# linistepper_with_aligned_transistors_my_.net
KiCad netlist of a schematic drawn in EAGLE
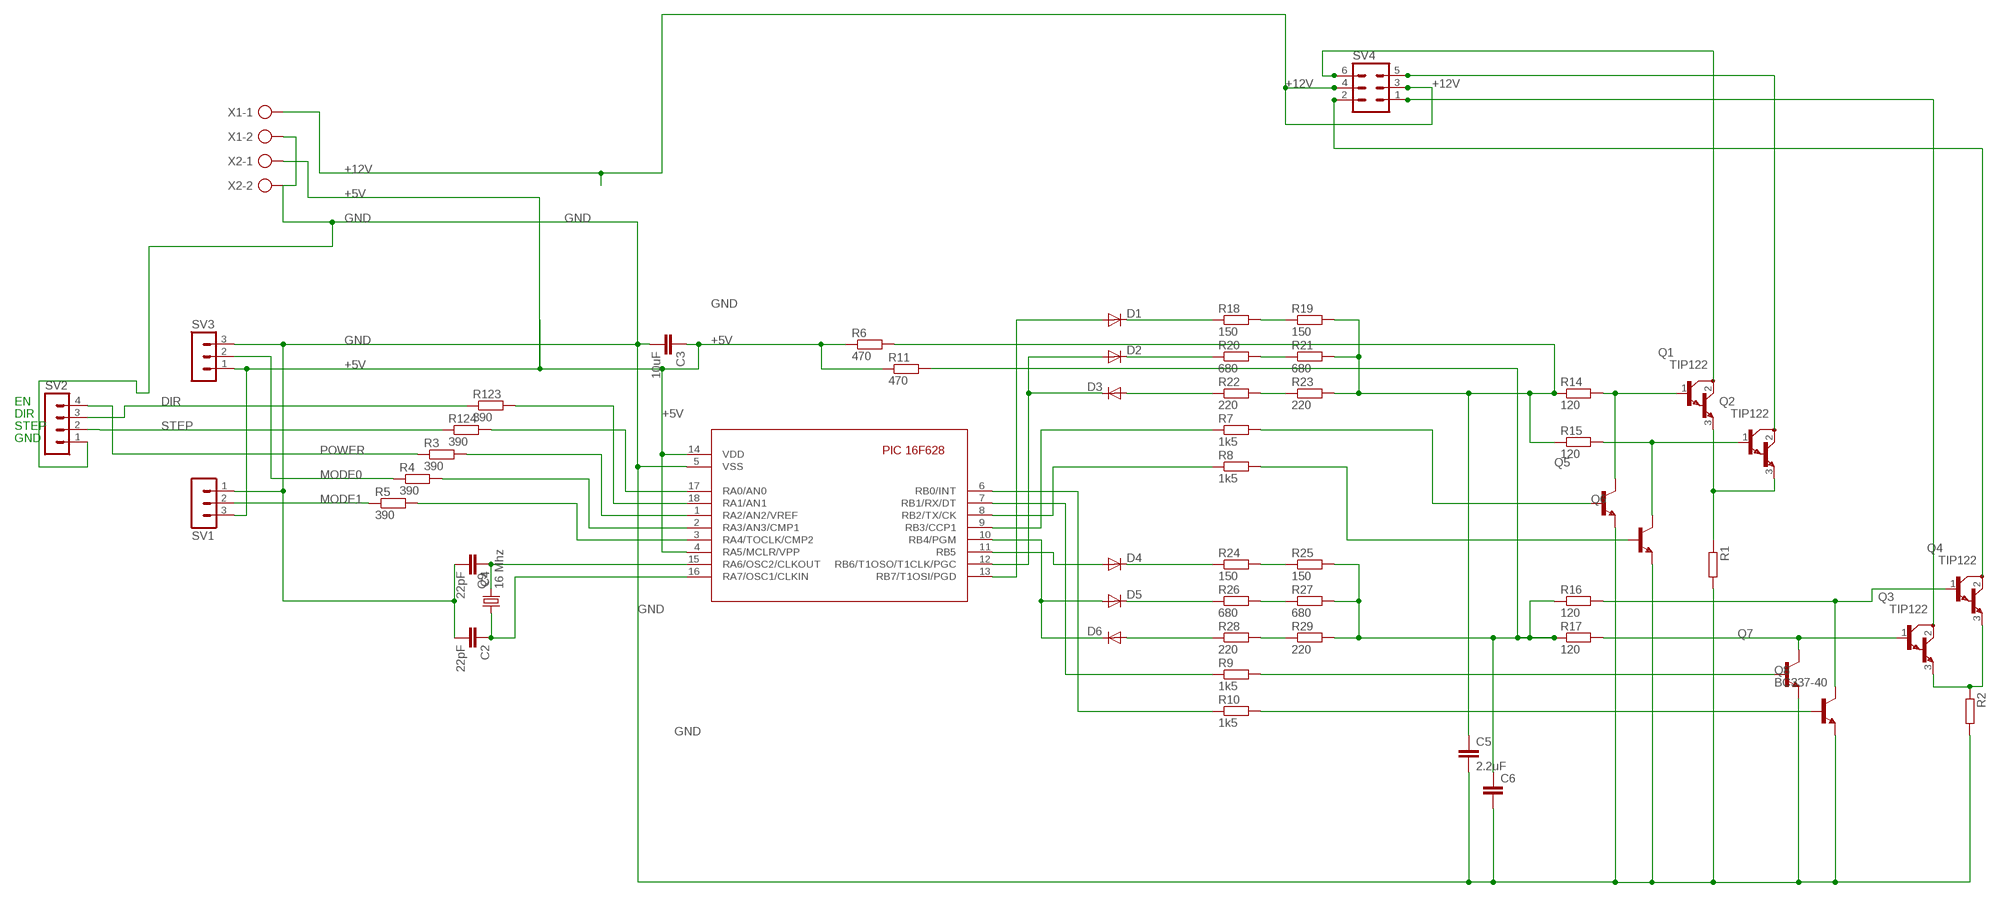
[diagram p0: schematic, sheet 1]

(export (version "E")
  (design (tool "Eeschema 10.0.6"))
  (components
    (comp (ref "C2")
      (value "22pF")
      (footprint "eagle-import:C025-024X044")
      (libsource (lib "eagle-import") (part "C-EU025-024X044"))
    )
    (comp (ref "C3")
      (value "10uF")
      (footprint "eagle-import:C025-040X050")
      (libsource (lib "eagle-import") (part "C-EU025-040X050"))
    )
    (comp (ref "C4")
      (value "22pF")
      (footprint "eagle-import:C025-024X044")
      (libsource (lib "eagle-import") (part "C-EU025-024X044"))
    )
    (comp (ref "C5")
      (value "2.2uF")
      (footprint "eagle-import:C050-024X044")
      (libsource (lib "eagle-import") (part "C-EU050-024X044"))
    )
    (comp (ref "C6")
      (value "C-EU050-024X044")
      (footprint "eagle-import:C050-024X044")
      (libsource (lib "eagle-import") (part "C-EU050-024X044"))
    )
    (comp (ref "D1")
      (value "1N4148")
      (footprint "eagle-import:DO35-10")
      (libsource (lib "eagle-import") (part "1N4148"))
    )
    (comp (ref "D2")
      (value "1N4148")
      (footprint "eagle-import:DO35-10")
      (libsource (lib "eagle-import") (part "1N4148"))
    )
    (comp (ref "D3")
      (value "1N4148")
      (footprint "eagle-import:DO35-10")
      (libsource (lib "eagle-import") (part "1N4148"))
    )
    (comp (ref "D4")
      (value "1N4148")
      (footprint "eagle-import:DO35-10")
      (libsource (lib "eagle-import") (part "1N4148"))
    )
    (comp (ref "D5")
      (value "1N4148")
      (footprint "eagle-import:DO35-10")
      (libsource (lib "eagle-import") (part "1N4148"))
    )
    (comp (ref "D6")
      (value "1N4148")
      (footprint "eagle-import:DO35-10")
      (libsource (lib "eagle-import") (part "1N4148"))
    )
    (comp (ref "Q1")
      (value "TIP122")
      (footprint "eagle-import:TO220")
      (libsource (lib "eagle-import") (part "TIP122"))
    )
    (comp (ref "Q2")
      (value "TIP122")
      (footprint "eagle-import:TO220")
      (libsource (lib "eagle-import") (part "TIP122"))
    )
    (comp (ref "Q3")
      (value "TIP122")
      (footprint "eagle-import:TO220")
      (libsource (lib "eagle-import") (part "TIP122"))
    )
    (comp (ref "Q4")
      (value "TIP122")
      (footprint "eagle-import:TO220")
      (libsource (lib "eagle-import") (part "TIP122"))
    )
    (comp (ref "Q5")
      (value "BC337-40")
      (footprint "eagle-import:TO92")
      (libsource (lib "eagle-import") (part "BC337-40"))
    )
    (comp (ref "Q6")
      (value "BC337-40")
      (footprint "eagle-import:TO92")
      (libsource (lib "eagle-import") (part "BC337-40"))
    )
    (comp (ref "Q7")
      (value "BC337-40")
      (footprint "eagle-import:TO92")
      (libsource (lib "eagle-import") (part "BC337-40"))
    )
    (comp (ref "Q8")
      (value "BC337-40")
      (footprint "eagle-import:TO92")
      (libsource (lib "eagle-import") (part "BC337-40"))
    )
    (comp (ref "Q9")
      (value "16 Mhz")
      (footprint "eagle-import:HC49_S")
      (libsource (lib "eagle-import") (part "CRYTALHC49S"))
    )
    (comp (ref "R1")
      (value "R-EU_0922/22")
      (footprint "eagle-import:0922_22")
      (libsource (lib "eagle-import") (part "R-EU_0922/22"))
    )
    (comp (ref "R2")
      (value "R-EU_0922/22")
      (footprint "eagle-import:0922_22")
      (libsource (lib "eagle-import") (part "R-EU_0922/22"))
    )
    (comp (ref "R3")
      (value "390")
      (footprint "eagle-import:0207_2V")
      (libsource (lib "eagle-import") (part "resistor_R-EU_0207/2V"))
    )
    (comp (ref "R4")
      (value "390")
      (footprint "eagle-import:0411V")
      (libsource (lib "eagle-import") (part "resistor_R-EU_0411/3V"))
    )
    (comp (ref "R5")
      (value "390")
      (footprint "eagle-import:0207_5V")
      (libsource (lib "eagle-import") (part "R-EU_0207/5V"))
    )
    (comp (ref "R6")
      (value "470")
      (footprint "eagle-import:0207_10")
      (libsource (lib "eagle-import") (part "R-EU_0207/10"))
    )
    (comp (ref "R7")
      (value "1k5")
      (footprint "eagle-import:0207_10")
      (libsource (lib "eagle-import") (part "R-EU_0207/10"))
    )
    (comp (ref "R8")
      (value "1k5")
      (footprint "eagle-import:0207_7")
      (libsource (lib "eagle-import") (part "resistor_R-EU_0207/7"))
    )
    (comp (ref "R9")
      (value "1k5")
      (footprint "eagle-import:0207_5V")
      (libsource (lib "eagle-import") (part "resistor_R-EU_0207/5V"))
    )
    (comp (ref "R10")
      (value "1k5")
      (footprint "eagle-import:0207_5V")
      (libsource (lib "eagle-import") (part "resistor_R-EU_0207/5V"))
    )
    (comp (ref "R11")
      (value "470")
      (footprint "eagle-import:0207_7")
      (libsource (lib "eagle-import") (part "resistor_R-EU_0207/7"))
    )
    (comp (ref "R14")
      (value "120")
      (footprint "eagle-import:0207_10")
      (libsource (lib "eagle-import") (part "R-EU_0207/10"))
    )
    (comp (ref "R15")
      (value "120")
      (footprint "eagle-import:0207_7")
      (libsource (lib "eagle-import") (part "resistor_R-EU_0207/7"))
    )
    (comp (ref "R16")
      (value "120")
      (footprint "eagle-import:0207_5V")
      (libsource (lib "eagle-import") (part "resistor_R-EU_0207/5V"))
    )
    (comp (ref "R17")
      (value "120")
      (footprint "eagle-import:0207_5V")
      (libsource (lib "eagle-import") (part "resistor_R-EU_0207/5V"))
    )
    (comp (ref "R18")
      (value "150")
      (footprint "eagle-import:0207_2V")
      (libsource (lib "eagle-import") (part "R-EU_0207/2V"))
    )
    (comp (ref "R19")
      (value "150")
      (footprint "eagle-import:0207_2V")
      (libsource (lib "eagle-import") (part "R-EU_0207/2V"))
    )
    (comp (ref "R20")
      (value "680")
      (footprint "eagle-import:0207_2V")
      (libsource (lib "eagle-import") (part "R-EU_0207/2V"))
    )
    (comp (ref "R21")
      (value "680")
      (footprint "eagle-import:0207_2V")
      (libsource (lib "eagle-import") (part "R-EU_0207/2V"))
    )
    (comp (ref "R22")
      (value "220")
      (footprint "eagle-import:0207_2V")
      (libsource (lib "eagle-import") (part "R-EU_0207/2V"))
    )
    (comp (ref "R23")
      (value "220")
      (footprint "eagle-import:0207_2V")
      (libsource (lib "eagle-import") (part "R-EU_0207/2V"))
    )
    (comp (ref "R24")
      (value "150")
      (footprint "eagle-import:0207_2V")
      (libsource (lib "eagle-import") (part "R-EU_0207/2V"))
    )
    (comp (ref "R25")
      (value "150")
      (footprint "eagle-import:0207_2V")
      (libsource (lib "eagle-import") (part "R-EU_0207/2V"))
    )
    (comp (ref "R26")
      (value "680")
      (footprint "eagle-import:0207_2V")
      (libsource (lib "eagle-import") (part "R-EU_0207/2V"))
    )
    (comp (ref "R27")
      (value "680")
      (footprint "eagle-import:0207_2V")
      (libsource (lib "eagle-import") (part "R-EU_0207/2V"))
    )
    (comp (ref "R28")
      (value "220")
      (footprint "eagle-import:0207_2V")
      (libsource (lib "eagle-import") (part "R-EU_0207/2V"))
    )
    (comp (ref "R29")
      (value "220")
      (footprint "eagle-import:0207_2V")
      (libsource (lib "eagle-import") (part "R-EU_0207/2V"))
    )
    (comp (ref "R123")
      (value "390")
      (footprint "eagle-import:0207_2V")
      (libsource (lib "eagle-import") (part "R-EU_0207/2V"))
    )
    (comp (ref "R124")
      (value "390")
      (footprint "eagle-import:0207_2V")
      (libsource (lib "eagle-import") (part "R-EU_0207/2V"))
    )
    (comp (ref "SV1")
      (value "MA03-1")
      (footprint "eagle-import:MA03-1")
      (libsource (lib "eagle-import") (part "MA03-1"))
    )
    (comp (ref "SV2")
      (value "MA04-1")
      (footprint "eagle-import:MA04-1")
      (libsource (lib "eagle-import") (part "MA04-1"))
    )
    (comp (ref "SV3")
      (value "MA03-1")
      (footprint "eagle-import:MA03-1")
      (libsource (lib "eagle-import") (part "MA03-1"))
    )
    (comp (ref "SV4")
      (value "MA03-2")
      (footprint "eagle-import:MA03-2")
      (libsource (lib "eagle-import") (part "MA03-2"))
    )
    (comp (ref "U$1")
      (value "16F628")
      (footprint "eagle-import:PIC16F628-18-LEAD-PDIP")
      (libsource (lib "eagle-import") (part "16F628"))
    )
    (comp (ref "X1")
      (value "AK300/2")
      (footprint "eagle-import:AK300_2")
      (libsource (lib "eagle-import") (part "AK300/2"))
    )
    (comp (ref "X2")
      (value "AK300/2")
      (footprint "eagle-import:AK300_2")
      (libsource (lib "eagle-import") (part "AK300/2"))
    )
  )
  (nets
    (net (code "1") (name "/+5V") (class "Default")
      (node (ref "C3") (pin "1") (pinfunction "1_1") (pintype "passive"))
      (node (ref "R11") (pin "1") (pinfunction "1_1") (pintype "passive"))
      (node (ref "R6") (pin "1") (pinfunction "1_1") (pintype "passive"))
      (node (ref "SV1") (pin "3") (pinfunction "3_3") (pintype "passive"))
      (node (ref "SV3") (pin "1") (pinfunction "1_1") (pintype "passive"))
      (node (ref "U$1") (pin "14") (pinfunction "VDD_14") (pintype "input"))
      (node (ref "U$1") (pin "4") (pinfunction "RA5/MCLR/VPP_4") (pintype "bidirectional"))
      (node (ref "X2") (pin "1") (pinfunction "KL_1") (pintype "passive"))
    )
    (net (code "2") (name "/+12V") (class "Default")
      (node (ref "SV4") (pin "3") (pinfunction "3_3") (pintype "passive"))
      (node (ref "SV4") (pin "4") (pinfunction "4_4") (pintype "passive"))
      (node (ref "X1") (pin "1") (pinfunction "KL_1") (pintype "passive"))
    )
    (net (code "3") (name "/DIR") (class "Default")
      (node (ref "R123") (pin "1") (pinfunction "1_1") (pintype "passive"))
      (node (ref "SV2") (pin "3") (pinfunction "3_3") (pintype "passive"))
    )
    (net (code "4") (name "/GND") (class "Default")
      (node (ref "C2") (pin "2") (pinfunction "2_2") (pintype "passive"))
      (node (ref "C3") (pin "2") (pinfunction "2_2") (pintype "passive"))
      (node (ref "C4") (pin "2") (pinfunction "2_2") (pintype "passive"))
      (node (ref "C5") (pin "2") (pinfunction "2_2") (pintype "passive"))
      (node (ref "C6") (pin "2") (pinfunction "2_2") (pintype "passive"))
      (node (ref "Q5") (pin "1") (pinfunction "E_1") (pintype "passive"))
      (node (ref "Q6") (pin "1") (pinfunction "E_1") (pintype "passive"))
      (node (ref "Q7") (pin "1") (pinfunction "E_1") (pintype "passive"))
      (node (ref "Q8") (pin "1") (pinfunction "E_1") (pintype "passive"))
      (node (ref "R1") (pin "2") (pinfunction "2_2") (pintype "passive"))
      (node (ref "R2") (pin "2") (pinfunction "2_2") (pintype "passive"))
      (node (ref "SV1") (pin "1") (pinfunction "1_1") (pintype "passive"))
      (node (ref "SV2") (pin "1") (pinfunction "1_1") (pintype "passive"))
      (node (ref "SV3") (pin "3") (pinfunction "3_3") (pintype "passive"))
      (node (ref "U$1") (pin "5") (pinfunction "VSS_5") (pintype "input"))
      (node (ref "X1") (pin "2") (pinfunction "KL_2") (pintype "passive"))
      (node (ref "X2") (pin "2") (pinfunction "KL_2") (pintype "passive"))
    )
    (net (code "5") (name "/MODE0") (class "Default")
      (node (ref "R4") (pin "1") (pinfunction "1_1") (pintype "passive"))
      (node (ref "SV3") (pin "2") (pinfunction "2_2") (pintype "passive"))
    )
    (net (code "6") (name "/MODE1") (class "Default")
      (node (ref "R5") (pin "1") (pinfunction "1_1") (pintype "passive"))
      (node (ref "SV1") (pin "2") (pinfunction "2_2") (pintype "passive"))
    )
    (net (code "7") (name "/POWER") (class "Default")
      (node (ref "R3") (pin "1") (pinfunction "1_1") (pintype "passive"))
      (node (ref "SV2") (pin "4") (pinfunction "4_4") (pintype "passive"))
    )
    (net (code "8") (name "/STEP") (class "Default")
      (node (ref "R124") (pin "1") (pinfunction "1_1") (pintype "passive"))
      (node (ref "SV2") (pin "2") (pinfunction "2_2") (pintype "passive"))
    )
    (net (code "9") (name "Net-(C5-Pad1)") (class "Default")
      (node (ref "C5") (pin "1") (pinfunction "1_1") (pintype "passive"))
      (node (ref "R14") (pin "1") (pinfunction "1_1") (pintype "passive"))
      (node (ref "R15") (pin "1") (pinfunction "1_1") (pintype "passive"))
      (node (ref "R19") (pin "2") (pinfunction "2_2") (pintype "passive"))
      (node (ref "R21") (pin "2") (pinfunction "2_2") (pintype "passive"))
      (node (ref "R23") (pin "2") (pinfunction "2_2") (pintype "passive"))
      (node (ref "R6") (pin "2") (pinfunction "2_2") (pintype "passive"))
    )
    (net (code "10") (name "Net-(C6-Pad1)") (class "Default")
      (node (ref "C6") (pin "1") (pinfunction "1_1") (pintype "passive"))
      (node (ref "R11") (pin "2") (pinfunction "2_2") (pintype "passive"))
      (node (ref "R16") (pin "1") (pinfunction "1_1") (pintype "passive"))
      (node (ref "R17") (pin "1") (pinfunction "1_1") (pintype "passive"))
      (node (ref "R25") (pin "2") (pinfunction "2_2") (pintype "passive"))
      (node (ref "R27") (pin "2") (pinfunction "2_2") (pintype "passive"))
      (node (ref "R29") (pin "2") (pinfunction "2_2") (pintype "passive"))
    )
    (net (code "11") (name "Net-(D1-PadC)") (class "Default")
      (node (ref "D1") (pin "C") (pinfunction "C_C") (pintype "passive"))
      (node (ref "R18") (pin "1") (pinfunction "1_1") (pintype "passive"))
    )
    (net (code "12") (name "Net-(D2-PadC)") (class "Default")
      (node (ref "D2") (pin "C") (pinfunction "C_C") (pintype "passive"))
      (node (ref "R20") (pin "1") (pinfunction "1_1") (pintype "passive"))
    )
    (net (code "13") (name "Net-(D3-PadA)") (class "Default")
      (node (ref "D3") (pin "A") (pinfunction "A_A") (pintype "passive"))
      (node (ref "R22") (pin "1") (pinfunction "1_1") (pintype "passive"))
    )
    (net (code "14") (name "Net-(D4-PadC)") (class "Default")
      (node (ref "D4") (pin "C") (pinfunction "C_C") (pintype "passive"))
      (node (ref "R24") (pin "1") (pinfunction "1_1") (pintype "passive"))
    )
    (net (code "15") (name "Net-(D5-PadC)") (class "Default")
      (node (ref "D5") (pin "C") (pinfunction "C_C") (pintype "passive"))
      (node (ref "R26") (pin "1") (pinfunction "1_1") (pintype "passive"))
    )
    (net (code "16") (name "Net-(D6-PadA)") (class "Default")
      (node (ref "D6") (pin "A") (pinfunction "A_A") (pintype "passive"))
      (node (ref "R28") (pin "1") (pinfunction "1_1") (pintype "passive"))
    )
    (net (code "17") (name "Net-(Q1-B)") (class "Default")
      (node (ref "Q1") (pin "1") (pinfunction "B_1") (pintype "passive"))
      (node (ref "Q5") (pin "3") (pinfunction "C_3") (pintype "passive"))
      (node (ref "R14") (pin "2") (pinfunction "2_2") (pintype "passive"))
    )
    (net (code "18") (name "Net-(Q1-C)") (class "Default")
      (node (ref "Q1") (pin "2") (pinfunction "C_2") (pintype "passive"))
      (node (ref "SV4") (pin "6") (pinfunction "6_6") (pintype "passive"))
    )
    (net (code "19") (name "Net-(Q1-E)") (class "Default")
      (node (ref "Q1") (pin "3") (pinfunction "E_3") (pintype "passive"))
      (node (ref "Q2") (pin "3") (pinfunction "E_3") (pintype "passive"))
      (node (ref "R1") (pin "1") (pinfunction "1_1") (pintype "passive"))
    )
    (net (code "20") (name "Net-(Q2-B)") (class "Default")
      (node (ref "Q2") (pin "1") (pinfunction "B_1") (pintype "passive"))
      (node (ref "Q6") (pin "3") (pinfunction "C_3") (pintype "passive"))
      (node (ref "R15") (pin "2") (pinfunction "2_2") (pintype "passive"))
    )
    (net (code "21") (name "Net-(Q2-C)") (class "Default")
      (node (ref "Q2") (pin "2") (pinfunction "C_2") (pintype "passive"))
      (node (ref "SV4") (pin "5") (pinfunction "5_5") (pintype "passive"))
    )
    (net (code "22") (name "Net-(Q3-B)") (class "Default")
      (node (ref "Q3") (pin "1") (pinfunction "B_1") (pintype "passive"))
      (node (ref "Q7") (pin "3") (pinfunction "C_3") (pintype "passive"))
      (node (ref "R17") (pin "2") (pinfunction "2_2") (pintype "passive"))
    )
    (net (code "23") (name "Net-(Q3-C)") (class "Default")
      (node (ref "Q3") (pin "2") (pinfunction "C_2") (pintype "passive"))
      (node (ref "SV4") (pin "1") (pinfunction "1_1") (pintype "passive"))
    )
    (net (code "24") (name "Net-(Q3-E)") (class "Default")
      (node (ref "Q3") (pin "3") (pinfunction "E_3") (pintype "passive"))
      (node (ref "Q4") (pin "3") (pinfunction "E_3") (pintype "passive"))
      (node (ref "R2") (pin "1") (pinfunction "1_1") (pintype "passive"))
    )
    (net (code "25") (name "Net-(Q4-B)") (class "Default")
      (node (ref "Q4") (pin "1") (pinfunction "B_1") (pintype "passive"))
      (node (ref "Q8") (pin "3") (pinfunction "C_3") (pintype "passive"))
      (node (ref "R16") (pin "2") (pinfunction "2_2") (pintype "passive"))
    )
    (net (code "26") (name "Net-(Q4-C)") (class "Default")
      (node (ref "Q4") (pin "2") (pinfunction "C_2") (pintype "passive"))
      (node (ref "SV4") (pin "2") (pinfunction "2_2") (pintype "passive"))
    )
    (net (code "27") (name "Net-(Q5-B)") (class "Default")
      (node (ref "Q5") (pin "2") (pinfunction "B_2") (pintype "passive"))
      (node (ref "R7") (pin "2") (pinfunction "2_2") (pintype "passive"))
    )
    (net (code "28") (name "Net-(Q6-B)") (class "Default")
      (node (ref "Q6") (pin "2") (pinfunction "B_2") (pintype "passive"))
      (node (ref "R8") (pin "2") (pinfunction "2_2") (pintype "passive"))
    )
    (net (code "29") (name "Net-(Q7-B)") (class "Default")
      (node (ref "Q7") (pin "2") (pinfunction "B_2") (pintype "passive"))
      (node (ref "R9") (pin "2") (pinfunction "2_2") (pintype "passive"))
    )
    (net (code "30") (name "Net-(Q8-B)") (class "Default")
      (node (ref "Q8") (pin "2") (pinfunction "B_2") (pintype "passive"))
      (node (ref "R10") (pin "2") (pinfunction "2_2") (pintype "passive"))
    )
    (net (code "31") (name "Net-(R18-Pad2)") (class "Default")
      (node (ref "R18") (pin "2") (pinfunction "2_2") (pintype "passive"))
      (node (ref "R19") (pin "1") (pinfunction "1_1") (pintype "passive"))
    )
    (net (code "32") (name "Net-(R20-Pad2)") (class "Default")
      (node (ref "R20") (pin "2") (pinfunction "2_2") (pintype "passive"))
      (node (ref "R21") (pin "1") (pinfunction "1_1") (pintype "passive"))
    )
    (net (code "33") (name "Net-(R22-Pad2)") (class "Default")
      (node (ref "R22") (pin "2") (pinfunction "2_2") (pintype "passive"))
      (node (ref "R23") (pin "1") (pinfunction "1_1") (pintype "passive"))
    )
    (net (code "34") (name "Net-(R24-Pad2)") (class "Default")
      (node (ref "R24") (pin "2") (pinfunction "2_2") (pintype "passive"))
      (node (ref "R25") (pin "1") (pinfunction "1_1") (pintype "passive"))
    )
    (net (code "35") (name "Net-(R26-Pad2)") (class "Default")
      (node (ref "R26") (pin "2") (pinfunction "2_2") (pintype "passive"))
      (node (ref "R27") (pin "1") (pinfunction "1_1") (pintype "passive"))
    )
    (net (code "36") (name "Net-(R28-Pad2)") (class "Default")
      (node (ref "R28") (pin "2") (pinfunction "2_2") (pintype "passive"))
      (node (ref "R29") (pin "1") (pinfunction "1_1") (pintype "passive"))
    )
    (net (code "37") (name "Net-(U$1-RA0{slash}AN0)") (class "Default")
      (node (ref "R124") (pin "2") (pinfunction "2_2") (pintype "passive"))
      (node (ref "U$1") (pin "17") (pinfunction "RA0/AN0_17") (pintype "bidirectional"))
    )
    (net (code "38") (name "Net-(U$1-RA1{slash}AN1)") (class "Default")
      (node (ref "R123") (pin "2") (pinfunction "2_2") (pintype "passive"))
      (node (ref "U$1") (pin "18") (pinfunction "RA1/AN1_18") (pintype "bidirectional"))
    )
    (net (code "39") (name "Net-(U$1-RA2{slash}AN2{slash}VREF)") (class "Default")
      (node (ref "R3") (pin "2") (pinfunction "2_2") (pintype "passive"))
      (node (ref "U$1") (pin "1") (pinfunction "RA2/AN2/VREF_1") (pintype "bidirectional"))
    )
    (net (code "40") (name "Net-(U$1-RA3{slash}AN3{slash}CMP1)") (class "Default")
      (node (ref "R4") (pin "2") (pinfunction "2_2") (pintype "passive"))
      (node (ref "U$1") (pin "2") (pinfunction "RA3/AN3/CMP1_2") (pintype "bidirectional"))
    )
    (net (code "41") (name "Net-(U$1-RA4{slash}TOCLK{slash}CMP2)") (class "Default")
      (node (ref "R5") (pin "2") (pinfunction "2_2") (pintype "passive"))
      (node (ref "U$1") (pin "3") (pinfunction "RA4/TOCLK/CMP2_3") (pintype "bidirectional"))
    )
    (net (code "42") (name "Net-(U$1-RA6{slash}OSC2{slash}CLKOUT)") (class "Default")
      (node (ref "C4") (pin "1") (pinfunction "1_1") (pintype "passive"))
      (node (ref "Q9") (pin "2") (pinfunction "2_2") (pintype "passive"))
      (node (ref "U$1") (pin "15") (pinfunction "RA6/OSC2/CLKOUT_15") (pintype "bidirectional"))
    )
    (net (code "43") (name "Net-(U$1-RA7{slash}OSC1{slash}CLKIN)") (class "Default")
      (node (ref "C2") (pin "1") (pinfunction "1_1") (pintype "passive"))
      (node (ref "Q9") (pin "1") (pinfunction "1_1") (pintype "passive"))
      (node (ref "U$1") (pin "16") (pinfunction "RA7/OSC1/CLKIN_16") (pintype "bidirectional"))
    )
    (net (code "44") (name "Net-(U$1-RB0{slash}INT)") (class "Default")
      (node (ref "R10") (pin "1") (pinfunction "1_1") (pintype "passive"))
      (node (ref "U$1") (pin "6") (pinfunction "RB0/INT_6") (pintype "bidirectional"))
    )
    (net (code "45") (name "Net-(U$1-RB1{slash}RX{slash}DT)") (class "Default")
      (node (ref "R9") (pin "1") (pinfunction "1_1") (pintype "passive"))
      (node (ref "U$1") (pin "7") (pinfunction "RB1/RX/DT_7") (pintype "bidirectional"))
    )
    (net (code "46") (name "Net-(U$1-RB2{slash}TX{slash}CK)") (class "Default")
      (node (ref "R8") (pin "1") (pinfunction "1_1") (pintype "passive"))
      (node (ref "U$1") (pin "8") (pinfunction "RB2/TX/CK_8") (pintype "bidirectional"))
    )
    (net (code "47") (name "Net-(U$1-RB3{slash}CCP1)") (class "Default")
      (node (ref "R7") (pin "1") (pinfunction "1_1") (pintype "passive"))
      (node (ref "U$1") (pin "9") (pinfunction "RB3/CCP1_9") (pintype "bidirectional"))
    )
    (net (code "48") (name "Net-(U$1-RB4{slash}PGM)") (class "Default")
      (node (ref "D5") (pin "A") (pinfunction "A_A") (pintype "passive"))
      (node (ref "D6") (pin "C") (pinfunction "C_C") (pintype "passive"))
      (node (ref "U$1") (pin "10") (pinfunction "RB4/PGM_10") (pintype "bidirectional"))
    )
    (net (code "49") (name "Net-(U$1-RB5)") (class "Default")
      (node (ref "D4") (pin "A") (pinfunction "A_A") (pintype "passive"))
      (node (ref "U$1") (pin "11") (pinfunction "RB5_11") (pintype "bidirectional"))
    )
    (net (code "50") (name "Net-(U$1-RB6{slash}T1OSO{slash}T1CLK{slash}PGC)") (class "Default")
      (node (ref "D2") (pin "A") (pinfunction "A_A") (pintype "passive"))
      (node (ref "D3") (pin "C") (pinfunction "C_C") (pintype "passive"))
      (node (ref "U$1") (pin "12") (pinfunction "RB6/T1OSO/T1CLK/PGC_12") (pintype "bidirectional"))
    )
    (net (code "51") (name "Net-(U$1-RB7{slash}T1OSI{slash}PGD)") (class "Default")
      (node (ref "D1") (pin "A") (pinfunction "A_A") (pintype "passive"))
      (node (ref "U$1") (pin "13") (pinfunction "RB7/T1OSI/PGD_13") (pintype "bidirectional"))
    )
  )
)
